# Ax2WDRobot.net
KiCad netlist of a schematic drawn in Altium Designer
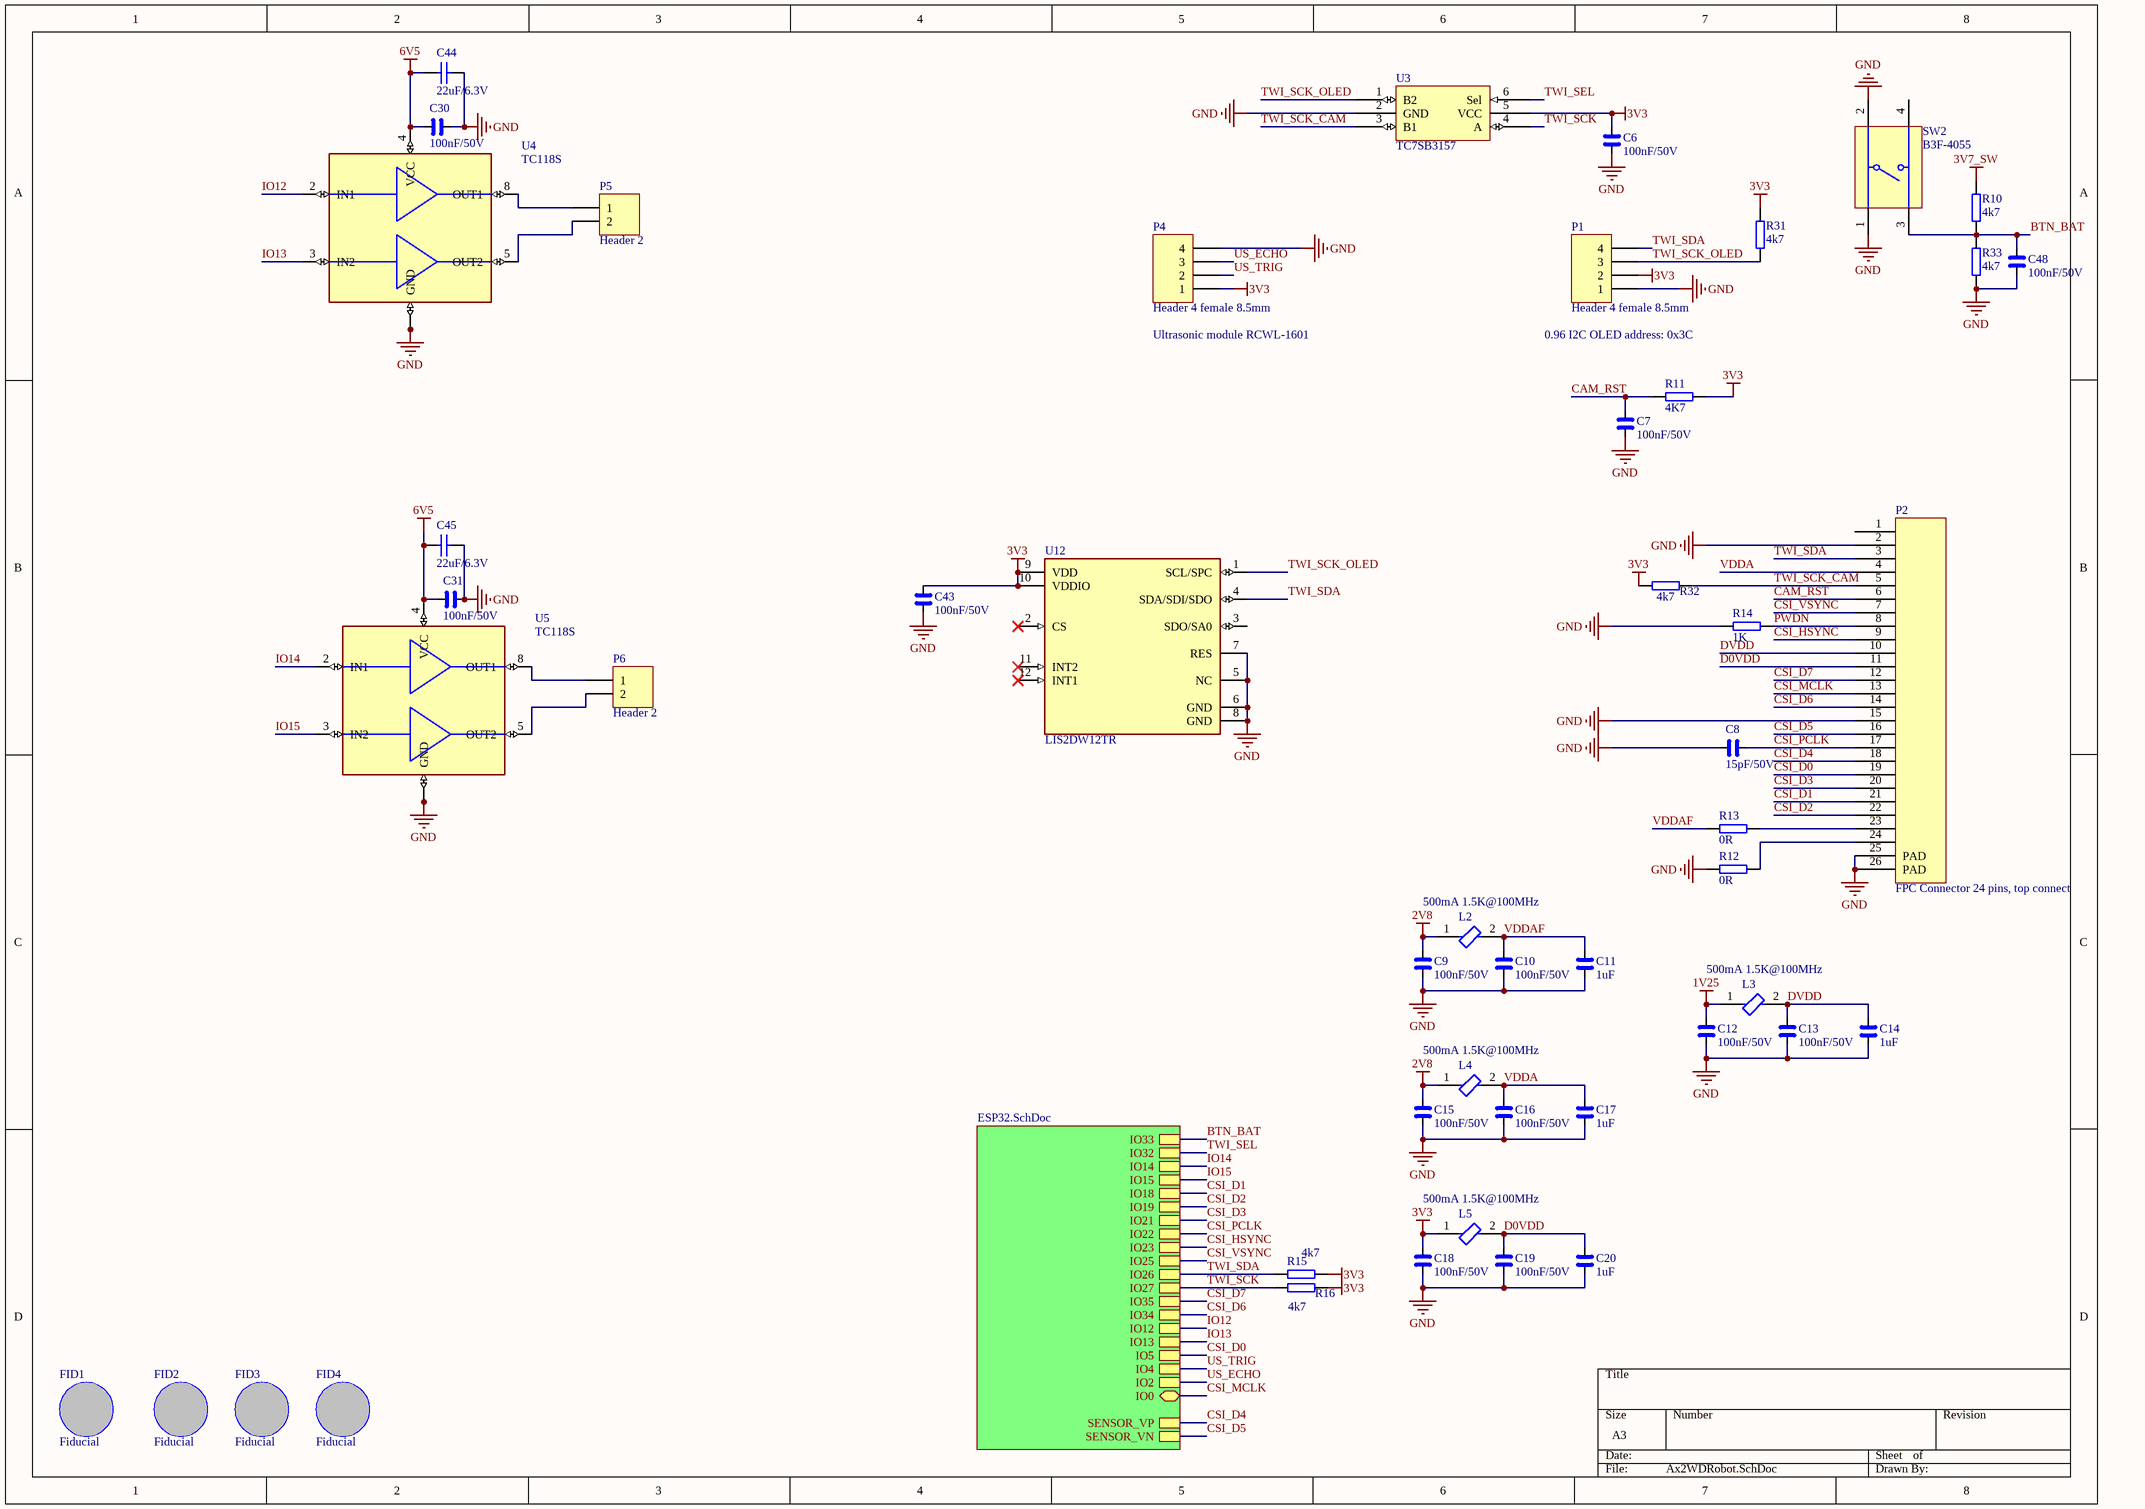
[diagram p0: Ax2WDRobot.SchDoc]

(export (version "E")
  (design (tool "Eeschema 10.0.6"))
  (components
    (comp (ref "C6")
      (value "100nF/50V")
      (footprint "1608[0603]")
      (description "Cap Ceramic 0.1uF 50V X7R 20% SMD 0603 125C Paper T/R")
      (fields (field (name "LCSCPARTNO") "C14663"))
      (libsource (lib "Sch") (part "C"))
    )
    (comp (ref "C7")
      (value "100nF/50V")
      (footprint "1608[0603]")
      (description "Cap Ceramic 0.1uF 50V X7R 20% SMD 0603 125C Paper T/R")
      (fields (field (name "LCSCPARTNO") "C14663"))
      (libsource (lib "Sch") (part "C"))
    )
    (comp (ref "C8")
      (value "15pF/50V")
      (footprint "1608[0603]")
      (description "Cap Ceramic 0603")
      (fields (field (name "LCSCPARTNO") "C1644"))
      (libsource (lib "Sch") (part "C"))
    )
    (comp (ref "C9")
      (value "100nF/50V")
      (footprint "1608[0603]")
      (description "Cap Ceramic 0.1uF 50V X7R 20% SMD 0603 125C Paper T/R")
      (fields (field (name "LCSCPARTNO") "C14663"))
      (libsource (lib "Sch") (part "C"))
    )
    (comp (ref "C10")
      (value "100nF/50V")
      (footprint "1608[0603]")
      (description "Cap Ceramic 0.1uF 50V X7R 20% SMD 0603 125C Paper T/R")
      (fields (field (name "LCSCPARTNO") "C14663"))
      (libsource (lib "Sch") (part "C"))
    )
    (comp (ref "C11")
      (value "1uF")
      (footprint "1608[0603]")
      (description "CAP CER 1UF 10V X5R 0603")
      (fields (field (name "LCSCPARTNO") "C15849"))
      (libsource (lib "Sch") (part "C"))
    )
    (comp (ref "C12")
      (value "100nF/50V")
      (footprint "1608[0603]")
      (description "Cap Ceramic 0.1uF 50V X7R 20% SMD 0603 125C Paper T/R")
      (fields (field (name "LCSCPARTNO") "C14663"))
      (libsource (lib "Sch") (part "C"))
    )
    (comp (ref "C13")
      (value "100nF/50V")
      (footprint "1608[0603]")
      (description "Cap Ceramic 0.1uF 50V X7R 20% SMD 0603 125C Paper T/R")
      (fields (field (name "LCSCPARTNO") "C14663"))
      (libsource (lib "Sch") (part "C"))
    )
    (comp (ref "C14")
      (value "1uF")
      (footprint "1608[0603]")
      (description "CAP CER 1UF 10V X5R 0603")
      (fields (field (name "LCSCPARTNO") "C15849"))
      (libsource (lib "Sch") (part "C"))
    )
    (comp (ref "C15")
      (value "100nF/50V")
      (footprint "1608[0603]")
      (description "Cap Ceramic 0.1uF 50V X7R 20% SMD 0603 125C Paper T/R")
      (fields (field (name "LCSCPARTNO") "C14663"))
      (libsource (lib "Sch") (part "C"))
    )
    (comp (ref "C16")
      (value "100nF/50V")
      (footprint "1608[0603]")
      (description "Cap Ceramic 0.1uF 50V X7R 20% SMD 0603 125C Paper T/R")
      (fields (field (name "LCSCPARTNO") "C14663"))
      (libsource (lib "Sch") (part "C"))
    )
    (comp (ref "C17")
      (value "1uF")
      (footprint "1608[0603]")
      (description "CAP CER 1UF 10V X5R 0603")
      (fields (field (name "LCSCPARTNO") "C15849"))
      (libsource (lib "Sch") (part "C"))
    )
    (comp (ref "C18")
      (value "100nF/50V")
      (footprint "1608[0603]")
      (description "Cap Ceramic 0.1uF 50V X7R 20% SMD 0603 125C Paper T/R")
      (fields (field (name "LCSCPARTNO") "C14663"))
      (libsource (lib "Sch") (part "C"))
    )
    (comp (ref "C19")
      (value "100nF/50V")
      (footprint "1608[0603]")
      (description "Cap Ceramic 0.1uF 50V X7R 20% SMD 0603 125C Paper T/R")
      (fields (field (name "LCSCPARTNO") "C14663"))
      (libsource (lib "Sch") (part "C"))
    )
    (comp (ref "C20")
      (value "1uF")
      (footprint "1608[0603]")
      (description "CAP CER 1UF 10V X5R 0603")
      (fields (field (name "LCSCPARTNO") "C15849"))
      (libsource (lib "Sch") (part "C"))
    )
    (comp (ref "C30")
      (value "100nF/50V")
      (footprint "1608[0603]")
      (description "Cap Ceramic 0.1uF 50V X7R 20% SMD 0603 125C Paper T/R")
      (fields (field (name "LCSCPARTNO") "C14663"))
      (libsource (lib "Sch") (part "C"))
    )
    (comp (ref "C31")
      (value "100nF/50V")
      (footprint "1608[0603]")
      (description "Cap Ceramic 0.1uF 50V X7R 20% SMD 0603 125C Paper T/R")
      (fields (field (name "LCSCPARTNO") "C14663"))
      (libsource (lib "Sch") (part "C"))
    )
    (comp (ref "C43")
      (value "100nF/50V")
      (footprint "1608[0603]")
      (description "Cap Ceramic 0.1uF 50V X7R 20% SMD 0603 125C Paper T/R")
      (fields
        (field (name "MANUFACTURER") "Samsung")
        (field (name "MANUFACTURER PART NUMBER") "CL10B104MB8NNNC")
      )
      (libsource (lib "Sch") (part "C"))
    )
    (comp (ref "C44")
      (value "22uF/6.3V")
      (footprint "1608[0603]")
      (description "Capacitor")
      (fields (field (name "LCSCPARTNO") "C59461"))
      (libsource (lib "Miscellaneous Devices") (part "Cap"))
    )
    (comp (ref "C45")
      (value "22uF/6.3V")
      (footprint "1608[0603]")
      (description "Capacitor")
      (fields (field (name "LCSCPARTNO") "C59461"))
      (libsource (lib "Miscellaneous Devices") (part "Cap"))
    )
    (comp (ref "C48")
      (value "100nF/50V")
      (footprint "1608[0603]")
      (description "Cap Ceramic 0.1uF 50V X7R 20% SMD 0603 125C Paper T/R")
      (fields (field (name "LCSCPARTNO") "C14663"))
      (libsource (lib "Sch") (part "C"))
    )
    (comp (ref "FID1")
      (value "Fiducial")
      (footprint "FIDUCIAL_POLY")
      (libsource (lib "RJ45_Jack") (part "Fiducial"))
    )
    (comp (ref "FID2")
      (value "Fiducial")
      (footprint "FIDUCIAL_POLY")
      (libsource (lib "RJ45_Jack") (part "Fiducial"))
    )
    (comp (ref "FID3")
      (value "Fiducial")
      (footprint "FIDUCIAL_POLY")
      (libsource (lib "RJ45_Jack") (part "Fiducial"))
    )
    (comp (ref "FID4")
      (value "Fiducial")
      (footprint "FIDUCIAL_POLY")
      (libsource (lib "RJ45_Jack") (part "Fiducial"))
    )
    (comp (ref "L2")
      (value "500mA 1.5K@100MHz")
      (footprint "1608[0603]")
      (description "Chip Ferrite Bead, 0603, 1500Ω @ 100MHz, 0.5Ω, 25%, 500mA")
      (fields (field (name "LCSCPARTNO") "C82155"))
      (libsource (lib "Altium Content Vault") (part "5f30dd21d616792df468990f7003faa"))
    )
    (comp (ref "L3")
      (value "500mA 1.5K@100MHz")
      (footprint "1608[0603]")
      (description "Chip Ferrite Bead, 0603, 1500Ω @ 100MHz, 0.5Ω, 25%, 500mA")
      (fields (field (name "LCSCPARTNO") "C82155"))
      (libsource (lib "Altium Content Vault") (part "5f30dd21d616792df468990f7003faa"))
    )
    (comp (ref "L4")
      (value "500mA 1.5K@100MHz")
      (footprint "1608[0603]")
      (description "Chip Ferrite Bead, 0603, 1500Ω @ 100MHz, 0.5Ω, 25%, 500mA")
      (fields (field (name "LCSCPARTNO") "C82155"))
      (libsource (lib "Altium Content Vault") (part "5f30dd21d616792df468990f7003faa"))
    )
    (comp (ref "L5")
      (value "500mA 1.5K@100MHz")
      (footprint "1608[0603]")
      (description "Chip Ferrite Bead, 0603, 1500Ω @ 100MHz, 0.5Ω, 25%, 500mA")
      (fields (field (name "LCSCPARTNO") "C82155"))
      (libsource (lib "Altium Content Vault") (part "5f30dd21d616792df468990f7003faa"))
    )
    (comp (ref "P1")
      (value "Header 4 female 8.5mm")
      (footprint "BCS-104-L-S-TE")
      (description "Header, 4-Pin")
      (fields (field (name "LCSCPARTNO") "C124413"))
      (libsource (lib "Miscellaneous Connectors") (part "Header 4"))
    )
    (comp (ref "P2")
      (value "FPC Connector 24 pins, top connect")
      (footprint "AFC07-S24ECA-00")
      (fields (field (name "LCSCPARTNO") "C262643"))
      (libsource (lib "Cam1") (part "FPC-CONN-24"))
    )
    (comp (ref "P4")
      (value "Header 4 female 8.5mm")
      (footprint "BCS-104-L-S-TE")
      (description "Header, 4-Pin")
      (fields (field (name "LCSCPARTNO") "C124413"))
      (libsource (lib "Miscellaneous Connectors") (part "Header 4"))
    )
    (comp (ref "P5")
      (value "Header 2")
      (footprint "BCS-102-L-S-TE")
      (description "Header, 2-Pin")
      (fields (field (name "LCSCPARTNO") "C49661") (field (name "PUBLISHER") "Altium Limited"))
      (libsource (lib "Miscellaneous Connectors") (part "Header 2"))
    )
    (comp (ref "P6")
      (value "Header 2")
      (footprint "BCS-102-L-S-TE")
      (description "Header, 2-Pin")
      (fields (field (name "LCSCPARTNO") "C49661") (field (name "PUBLISHER") "Altium Limited"))
      (libsource (lib "Miscellaneous Connectors") (part "Header 2"))
    )
    (comp (ref "R10")
      (value "4k7")
      (footprint "1608[0603]")
      (description "RES SMD 4.7K OHM 1% 1/10W 0603")
      (fields (field (name "LCSCPARTNO") "C23162"))
      (libsource (lib "Sch") (part "R"))
    )
    (comp (ref "R11")
      (value "4K7")
      (footprint "1608[0603]")
      (description "Res General Purpose Thick Film 0603 1% 1/10W ±100ppm/°C Molded SMD Paper T/R")
      (fields (field (name "LCSCPARTNO") "C23162"))
      (libsource (lib "Sch") (part "R"))
    )
    (comp (ref "R12")
      (value "0R")
      (footprint "1608[0603]")
      (description "Res General Purpose Thick Film 0603 1% 1/10W ±100ppm/°C Molded SMD Paper T/R")
      (fields (field (name "LCSCPARTNO") "C21189"))
      (libsource (lib "Sch") (part "R"))
    )
    (comp (ref "R13")
      (value "0R")
      (footprint "1608[0603]")
      (description "Res General Purpose Thick Film 0603 1% 1/10W ±100ppm/°C Molded SMD Paper T/R")
      (fields (field (name "LCSCPARTNO") "C21189"))
      (libsource (lib "Sch") (part "R"))
    )
    (comp (ref "R14")
      (value "1K")
      (footprint "1608[0603]")
      (description "Res General Purpose Thick Film 0603 1% 1/10W ±100ppm/°C Molded SMD Paper T/R")
      (fields (field (name "LCSCPARTNO") "C21190"))
      (libsource (lib "Sch") (part "R"))
    )
    (comp (ref "R15")
      (value "4k7")
      (footprint "1608[0603]")
      (description "RES SMD 4.7K OHM 1% 1/10W 0603")
      (fields (field (name "LCSCPARTNO") "C23162"))
      (libsource (lib "Sch") (part "R"))
    )
    (comp (ref "R16")
      (value "4k7")
      (footprint "1608[0603]")
      (description "RES SMD 4.7K OHM 1% 1/10W 0603")
      (fields (field (name "LCSCPARTNO") "C23162"))
      (libsource (lib "Sch") (part "R"))
    )
    (comp (ref "R31")
      (value "4k7")
      (footprint "1608[0603]")
      (description "RES SMD 4.7K OHM 1% 1/10W 0603")
      (fields (field (name "LCSCPARTNO") "C23162"))
      (libsource (lib "Sch") (part "R"))
    )
    (comp (ref "R32")
      (value "4k7")
      (footprint "1608[0603]")
      (description "RES SMD 4.7K OHM 1% 1/10W 0603")
      (fields (field (name "LCSCPARTNO") "C23162"))
      (libsource (lib "Sch") (part "R"))
    )
    (comp (ref "R33")
      (value "4k7")
      (footprint "1608[0603]")
      (description "RES SMD 4.7K OHM 1% 1/10W 0603")
      (fields (field (name "LCSCPARTNO") "C23162"))
      (libsource (lib "Sch") (part "R"))
    )
    (comp (ref "SW2")
      (value "B3F-4055")
      (footprint "OMRON-B3F-4055_AX")
      (description "Tactile Switch, 1 to 50 mA, 100 mOhm Max, 5 to 24 VDC, -25 to 70 degC, 4-Pin THD, RoHS, Bulk")
      (fields (field (name "LCSCPARTNO") "C84931"))
      (libsource (lib "Omron_B3F-4055") (part "CMP-2000-05902-1"))
    )
    (comp (ref "U3")
      (value "TC7SB3157")
      (footprint "SOT-363_MP6D")
      (description "1-of-2 multiplexer/demultiplexer")
      (fields (field (name "LCSCPARTNO") "C2674458") (field (name "LCSCALTPARTNO") "C150170"))
      (libsource (lib "CombinedMultiplexerMainboard") (part "TC7SB3157CFU"))
    )
    (comp (ref "U4")
      (value "TC118S")
      (footprint "SO08")
      (fields (field (name "LCSCPARTNO") "C88308"))
      (libsource (lib "TC118S") (part "TC118S"))
    )
    (comp (ref "U5")
      (value "TC118S")
      (footprint "SO08")
      (fields (field (name "LCSCPARTNO") "C88308"))
      (libsource (lib "TC118S") (part "TC118S"))
    )
    (comp (ref "U12")
      (value "LIS2DW12TR")
      (footprint "FP-LGA12-DM00170568-MFG")
      (description "ACCEL 2-16G I2C/SPI 12LGA")
      (fields
        (field (name "OCTOPART") "https://octopart.com/lis2dw12tr-stmicroelectronics-77080925")
        (field (name "MANUFACTURER") "STMicroelectronics")
      )
      (libsource (lib "Altium Content Vault") (part "8197bdef8f004bf043f7592a5d62978"))
    )
  )
  (nets
    (net (code "1") (name "/BTN_BAT") (class "Default")
      (node (ref "C48") (pin "2") (pinfunction "2_2") (pintype "passive"))
      (node (ref "R10") (pin "1") (pintype "passive"))
      (node (ref "R33") (pin "2") (pintype "passive"))
      (node (ref "SW2") (pin "3") (pinfunction "3_3") (pintype "passive"))
    )
    (net (code "2") (name "/CAM_RST") (class "Default")
      (node (ref "C7") (pin "2") (pinfunction "2_2") (pintype "passive"))
      (node (ref "P2") (pin "6") (pintype "passive"))
      (node (ref "R11") (pin "1") (pintype "passive"))
    )
    (net (code "3") (name "/CSI_D0") (class "Default") (node (ref "P2") (pin "19") (pintype "passive")))
    (net (code "4") (name "/CSI_D1") (class "Default") (node (ref "P2") (pin "21") (pintype "passive")))
    (net (code "5") (name "/CSI_D2") (class "Default") (node (ref "P2") (pin "22") (pintype "passive")))
    (net (code "6") (name "/CSI_D3") (class "Default") (node (ref "P2") (pin "20") (pintype "passive")))
    (net (code "7") (name "/CSI_D4") (class "Default") (node (ref "P2") (pin "18") (pintype "passive")))
    (net (code "8") (name "/CSI_D5") (class "Default") (node (ref "P2") (pin "16") (pintype "passive")))
    (net (code "9") (name "/CSI_D6") (class "Default") (node (ref "P2") (pin "14") (pintype "passive")))
    (net (code "10") (name "/CSI_D7") (class "Default") (node (ref "P2") (pin "12") (pintype "passive")))
    (net (code "11") (name "/CSI_HSYNC") (class "Default") (node (ref "P2") (pin "9") (pintype "passive")))
    (net (code "12") (name "/CSI_MCLK") (class "Default") (node (ref "P2") (pin "13") (pintype "passive")))
    (net (code "13") (name "/CSI_PCLK") (class "Default")
      (node (ref "C8") (pin "2") (pinfunction "2_2") (pintype "passive"))
      (node (ref "P2") (pin "17") (pintype "passive"))
    )
    (net (code "14") (name "/CSI_VSYNC") (class "Default") (node (ref "P2") (pin "7") (pintype "passive")))
    (net (code "15") (name "/D0VDD") (class "Default")
      (node (ref "C19") (pin "2") (pinfunction "2_2") (pintype "passive"))
      (node (ref "C20") (pin "1") (pinfunction "1_1") (pintype "passive"))
      (node (ref "L5") (pin "2") (pinfunction "2_2") (pintype "passive"))
      (node (ref "P2") (pin "11") (pintype "passive"))
    )
    (net (code "16") (name "/DVDD") (class "Default")
      (node (ref "C13") (pin "2") (pinfunction "2_2") (pintype "passive"))
      (node (ref "C14") (pin "1") (pinfunction "1_1") (pintype "passive"))
      (node (ref "L3") (pin "2") (pinfunction "2_2") (pintype "passive"))
      (node (ref "P2") (pin "10") (pintype "passive"))
    )
    (net (code "17") (name "/IO12") (class "Default")
      (node (ref "U4") (pin "2") (pinfunction "IN1_2") (pintype "bidirectional"))
    )
    (net (code "18") (name "/IO13") (class "Default")
      (node (ref "U4") (pin "3") (pinfunction "IN2_3") (pintype "bidirectional"))
    )
    (net (code "19") (name "/IO14") (class "Default")
      (node (ref "U5") (pin "2") (pinfunction "IN1_2") (pintype "bidirectional"))
    )
    (net (code "20") (name "/IO15") (class "Default")
      (node (ref "U5") (pin "3") (pinfunction "IN2_3") (pintype "bidirectional"))
    )
    (net (code "21") (name "/PWDN") (class "Default")
      (node (ref "P2") (pin "8") (pintype "passive"))
      (node (ref "R14") (pin "2") (pintype "passive"))
    )
    (net (code "22") (name "/TWI_SCK") (class "Default")
      (node (ref "R16") (pin "2") (pintype "passive"))
      (node (ref "U3") (pin "4") (pinfunction "A_4") (pintype "bidirectional"))
    )
    (net (code "23") (name "/TWI_SCK_CAM") (class "Default")
      (node (ref "P2") (pin "5") (pintype "passive"))
      (node (ref "R32") (pin "1") (pintype "passive"))
      (node (ref "U3") (pin "3") (pinfunction "B1_3") (pintype "bidirectional"))
    )
    (net (code "24") (name "/TWI_SCK_OLED") (class "Default")
      (node (ref "P1") (pin "3") (pinfunction "3_3") (pintype "passive"))
      (node (ref "R31") (pin "1") (pintype "passive"))
      (node (ref "U12") (pin "1") (pinfunction "SCL/SPC_1") (pintype "bidirectional"))
      (node (ref "U3") (pin "1") (pinfunction "B2_1") (pintype "bidirectional"))
    )
    (net (code "25") (name "/TWI_SDA") (class "Default")
      (node (ref "P1") (pin "4") (pinfunction "4_4") (pintype "passive"))
      (node (ref "P2") (pin "3") (pintype "passive"))
      (node (ref "R15") (pin "2") (pintype "passive"))
      (node (ref "U12") (pin "4") (pinfunction "SDA/SDI/SDO_4") (pintype "bidirectional"))
    )
    (net (code "26") (name "/TWI_SEL") (class "Default")
      (node (ref "U3") (pin "6") (pinfunction "Sel_6") (pintype "input"))
    )
    (net (code "27") (name "/US_ECHO") (class "Default")
      (node (ref "P4") (pin "3") (pinfunction "3_3") (pintype "passive"))
    )
    (net (code "28") (name "/US_TRIG") (class "Default")
      (node (ref "P4") (pin "2") (pinfunction "2_2") (pintype "passive"))
    )
    (net (code "29") (name "/VDDA") (class "Default")
      (node (ref "C16") (pin "2") (pinfunction "2_2") (pintype "passive"))
      (node (ref "C17") (pin "1") (pinfunction "1_1") (pintype "passive"))
      (node (ref "L4") (pin "2") (pinfunction "2_2") (pintype "passive"))
      (node (ref "P2") (pin "4") (pintype "passive"))
    )
    (net (code "30") (name "/VDDAF") (class "Default")
      (node (ref "C10") (pin "2") (pinfunction "2_2") (pintype "passive"))
      (node (ref "C11") (pin "1") (pinfunction "1_1") (pintype "passive"))
      (node (ref "L2") (pin "2") (pinfunction "2_2") (pintype "passive"))
      (node (ref "R13") (pin "1") (pintype "passive"))
    )
    (net (code "31") (name "1V25") (class "Default")
      (node (ref "C12") (pin "2") (pinfunction "2_2") (pintype "passive"))
      (node (ref "L3") (pin "1") (pinfunction "1_1") (pintype "passive"))
    )
    (net (code "32") (name "2V8") (class "Default")
      (node (ref "C15") (pin "2") (pinfunction "2_2") (pintype "passive"))
      (node (ref "C9") (pin "2") (pinfunction "2_2") (pintype "passive"))
      (node (ref "L2") (pin "1") (pinfunction "1_1") (pintype "passive"))
      (node (ref "L4") (pin "1") (pinfunction "1_1") (pintype "passive"))
    )
    (net (code "33") (name "3V3") (class "Default")
      (node (ref "C18") (pin "2") (pinfunction "2_2") (pintype "passive"))
      (node (ref "C43") (pin "1") (pinfunction "1_1") (pintype "passive"))
      (node (ref "C6") (pin "1") (pinfunction "1_1") (pintype "passive"))
      (node (ref "L5") (pin "1") (pinfunction "1_1") (pintype "passive"))
      (node (ref "P1") (pin "2") (pinfunction "2_2") (pintype "passive"))
      (node (ref "P4") (pin "1") (pinfunction "1_1") (pintype "passive"))
      (node (ref "R11") (pin "2") (pintype "passive"))
      (node (ref "R15") (pin "1") (pintype "passive"))
      (node (ref "R16") (pin "1") (pintype "passive"))
      (node (ref "R31") (pin "2") (pintype "passive"))
      (node (ref "R32") (pin "2") (pintype "passive"))
      (node (ref "U12") (pin "10") (pinfunction "VDDIO_10") (pintype "power_in"))
      (node (ref "U12") (pin "9") (pinfunction "VDD_9") (pintype "power_in"))
      (node (ref "U3") (pin "5") (pinfunction "VCC_5") (pintype "power_in"))
    )
    (net (code "34") (name "3V7_SW") (class "Default") (node (ref "R10") (pin "2") (pintype "passive")))
    (net (code "35") (name "6V5") (class "Default")
      (node (ref "C30") (pin "2") (pinfunction "2_2") (pintype "passive"))
      (node (ref "C31") (pin "2") (pinfunction "2_2") (pintype "passive"))
      (node (ref "C44") (pin "2") (pinfunction "2_2") (pintype "passive"))
      (node (ref "C45") (pin "2") (pinfunction "2_2") (pintype "passive"))
      (node (ref "U4") (pin "4") (pinfunction "VCC_4") (pintype "bidirectional"))
      (node (ref "U5") (pin "4") (pinfunction "VCC_4") (pintype "bidirectional"))
    )
    (net (code "36") (name "GND") (class "Default")
      (node (ref "C10") (pin "1") (pinfunction "1_1") (pintype "passive"))
      (node (ref "C11") (pin "2") (pinfunction "2_2") (pintype "passive"))
      (node (ref "C12") (pin "1") (pinfunction "1_1") (pintype "passive"))
      (node (ref "C13") (pin "1") (pinfunction "1_1") (pintype "passive"))
      (node (ref "C14") (pin "2") (pinfunction "2_2") (pintype "passive"))
      (node (ref "C15") (pin "1") (pinfunction "1_1") (pintype "passive"))
      (node (ref "C16") (pin "1") (pinfunction "1_1") (pintype "passive"))
      (node (ref "C17") (pin "2") (pinfunction "2_2") (pintype "passive"))
      (node (ref "C18") (pin "1") (pinfunction "1_1") (pintype "passive"))
      (node (ref "C19") (pin "1") (pinfunction "1_1") (pintype "passive"))
      (node (ref "C20") (pin "2") (pinfunction "2_2") (pintype "passive"))
      (node (ref "C30") (pin "1") (pinfunction "1_1") (pintype "passive"))
      (node (ref "C31") (pin "1") (pinfunction "1_1") (pintype "passive"))
      (node (ref "C43") (pin "2") (pinfunction "2_2") (pintype "passive"))
      (node (ref "C44") (pin "1") (pinfunction "1_1") (pintype "passive"))
      (node (ref "C45") (pin "1") (pinfunction "1_1") (pintype "passive"))
      (node (ref "C48") (pin "1") (pinfunction "1_1") (pintype "passive"))
      (node (ref "C6") (pin "2") (pinfunction "2_2") (pintype "passive"))
      (node (ref "C7") (pin "1") (pinfunction "1_1") (pintype "passive"))
      (node (ref "C8") (pin "1") (pinfunction "1_1") (pintype "passive"))
      (node (ref "C9") (pin "1") (pinfunction "1_1") (pintype "passive"))
      (node (ref "P1") (pin "1") (pinfunction "1_1") (pintype "passive"))
      (node (ref "P2") (pin "15") (pintype "passive"))
      (node (ref "P2") (pin "2") (pintype "passive"))
      (node (ref "P2") (pin "25") (pinfunction "PAD_25") (pintype "passive"))
      (node (ref "P2") (pin "26") (pinfunction "PAD_26") (pintype "passive"))
      (node (ref "P4") (pin "4") (pinfunction "4_4") (pintype "passive"))
      (node (ref "R12") (pin "1") (pintype "passive"))
      (node (ref "R14") (pin "1") (pintype "passive"))
      (node (ref "R33") (pin "1") (pintype "passive"))
      (node (ref "SW2") (pin "1") (pinfunction "1_1") (pintype "passive"))
      (node (ref "SW2") (pin "2") (pinfunction "2_2") (pintype "passive"))
      (node (ref "U12") (pin "5") (pinfunction "NC_5") (pintype "passive"))
      (node (ref "U12") (pin "6") (pinfunction "GND_6") (pintype "power_in"))
      (node (ref "U12") (pin "7") (pinfunction "RES_7") (pintype "passive"))
      (node (ref "U12") (pin "8") (pinfunction "GND_8") (pintype "power_in"))
      (node (ref "U3") (pin "2") (pinfunction "GND_2") (pintype "power_in"))
      (node (ref "U4") (pin "6") (pinfunction "GND_6") (pintype "bidirectional"))
      (node (ref "U4") (pin "7") (pinfunction "GND_7") (pintype "bidirectional"))
      (node (ref "U5") (pin "6") (pinfunction "GND_6") (pintype "bidirectional"))
      (node (ref "U5") (pin "7") (pinfunction "GND_7") (pintype "bidirectional"))
    )
    (net (code "37") (name "Net-(P2-Pad23)") (class "Default")
      (node (ref "P2") (pin "23") (pintype "passive"))
      (node (ref "R13") (pin "2") (pintype "passive"))
    )
    (net (code "38") (name "Net-(P2-Pad24)") (class "Default")
      (node (ref "P2") (pin "24") (pintype "passive"))
      (node (ref "R12") (pin "2") (pintype "passive"))
    )
    (net (code "39") (name "Net-(U4-OUT1)") (class "Default")
      (node (ref "P5") (pin "1") (pinfunction "1_1") (pintype "passive"))
      (node (ref "U4") (pin "8") (pinfunction "OUT1_8") (pintype "bidirectional"))
    )
    (net (code "40") (name "Net-(U4-OUT2)") (class "Default")
      (node (ref "P5") (pin "2") (pinfunction "2_2") (pintype "passive"))
      (node (ref "U4") (pin "5") (pinfunction "OUT2_5") (pintype "bidirectional"))
    )
    (net (code "41") (name "Net-(U5-OUT1)") (class "Default")
      (node (ref "P6") (pin "1") (pinfunction "1_1") (pintype "passive"))
      (node (ref "U5") (pin "8") (pinfunction "OUT1_8") (pintype "bidirectional"))
    )
    (net (code "42") (name "Net-(U5-OUT2)") (class "Default")
      (node (ref "P6") (pin "2") (pinfunction "2_2") (pintype "passive"))
      (node (ref "U5") (pin "5") (pinfunction "OUT2_5") (pintype "bidirectional"))
    )
    (net (code "43") (name "unconnected-(P2-Pad1)") (class "Default")
      (node (ref "P2") (pin "1") (pintype "passive"))
    )
    (net (code "44") (name "unconnected-(SW2-Pad4)") (class "Default")
      (node (ref "SW2") (pin "4") (pinfunction "4_4") (pintype "passive"))
    )
    (net (code "45") (name "unconnected-(U12-CS-Pad2)") (class "Default")
      (node (ref "U12") (pin "2") (pinfunction "CS_2") (pintype "input+no_connect"))
    )
    (net (code "46") (name "unconnected-(U12-INT1-Pad12)") (class "Default")
      (node (ref "U12") (pin "12") (pinfunction "INT1_12") (pintype "input+no_connect"))
    )
    (net (code "47") (name "unconnected-(U12-INT2-Pad11)") (class "Default")
      (node (ref "U12") (pin "11") (pinfunction "INT2_11") (pintype "input+no_connect"))
    )
    (net (code "48") (name "unconnected-(U12-SDO{slash}SA0-Pad3)") (class "Default")
      (node (ref "U12") (pin "3") (pinfunction "SDO/SA0_3") (pintype "bidirectional"))
    )
  )
)
